# MOUNTING_HOLE.net
KiCad netlist of a schematic drawn in Altium Designer
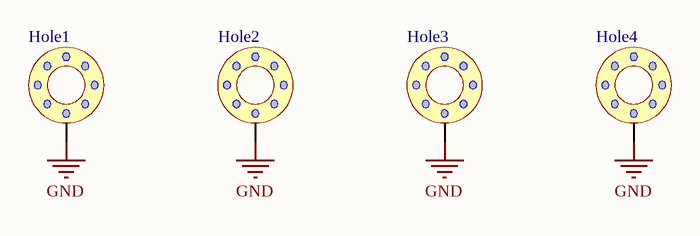
[diagram p0: MOUNTING_HOLE.SchDoc]

(export (version "E")
  (design (tool "Eeschema 10.0.6"))
  (components
    (comp (ref "Hole1")
      (value "hole_space")
      (footprint "HEX-M3_NoVia")
      (libsource (lib "IFBschelib") (part "hole_space"))
    )
    (comp (ref "Hole2")
      (value "hole_space")
      (footprint "HEX-M3_NoVia")
      (libsource (lib "IFBschelib") (part "hole_space"))
    )
    (comp (ref "Hole3")
      (value "hole_space")
      (footprint "HEX-M3_NoVia")
      (libsource (lib "IFBschelib") (part "hole_space"))
    )
    (comp (ref "Hole4")
      (value "hole_space")
      (footprint "HEX-M3_NoVia")
      (libsource (lib "IFBschelib") (part "hole_space"))
    )
  )
  (nets
    (net (code "1") (name "GND") (class "Default")
      (node (ref "Hole1") (pin "1") (pinfunction "1_1") (pintype "passive"))
      (node (ref "Hole2") (pin "1") (pinfunction "1_1") (pintype "passive"))
      (node (ref "Hole3") (pin "1") (pinfunction "1_1") (pintype "passive"))
      (node (ref "Hole4") (pin "1") (pinfunction "1_1") (pintype "passive"))
    )
  )
)
